# GridEye_STM32.net
KiCad netlist of a schematic drawn in Altium Designer
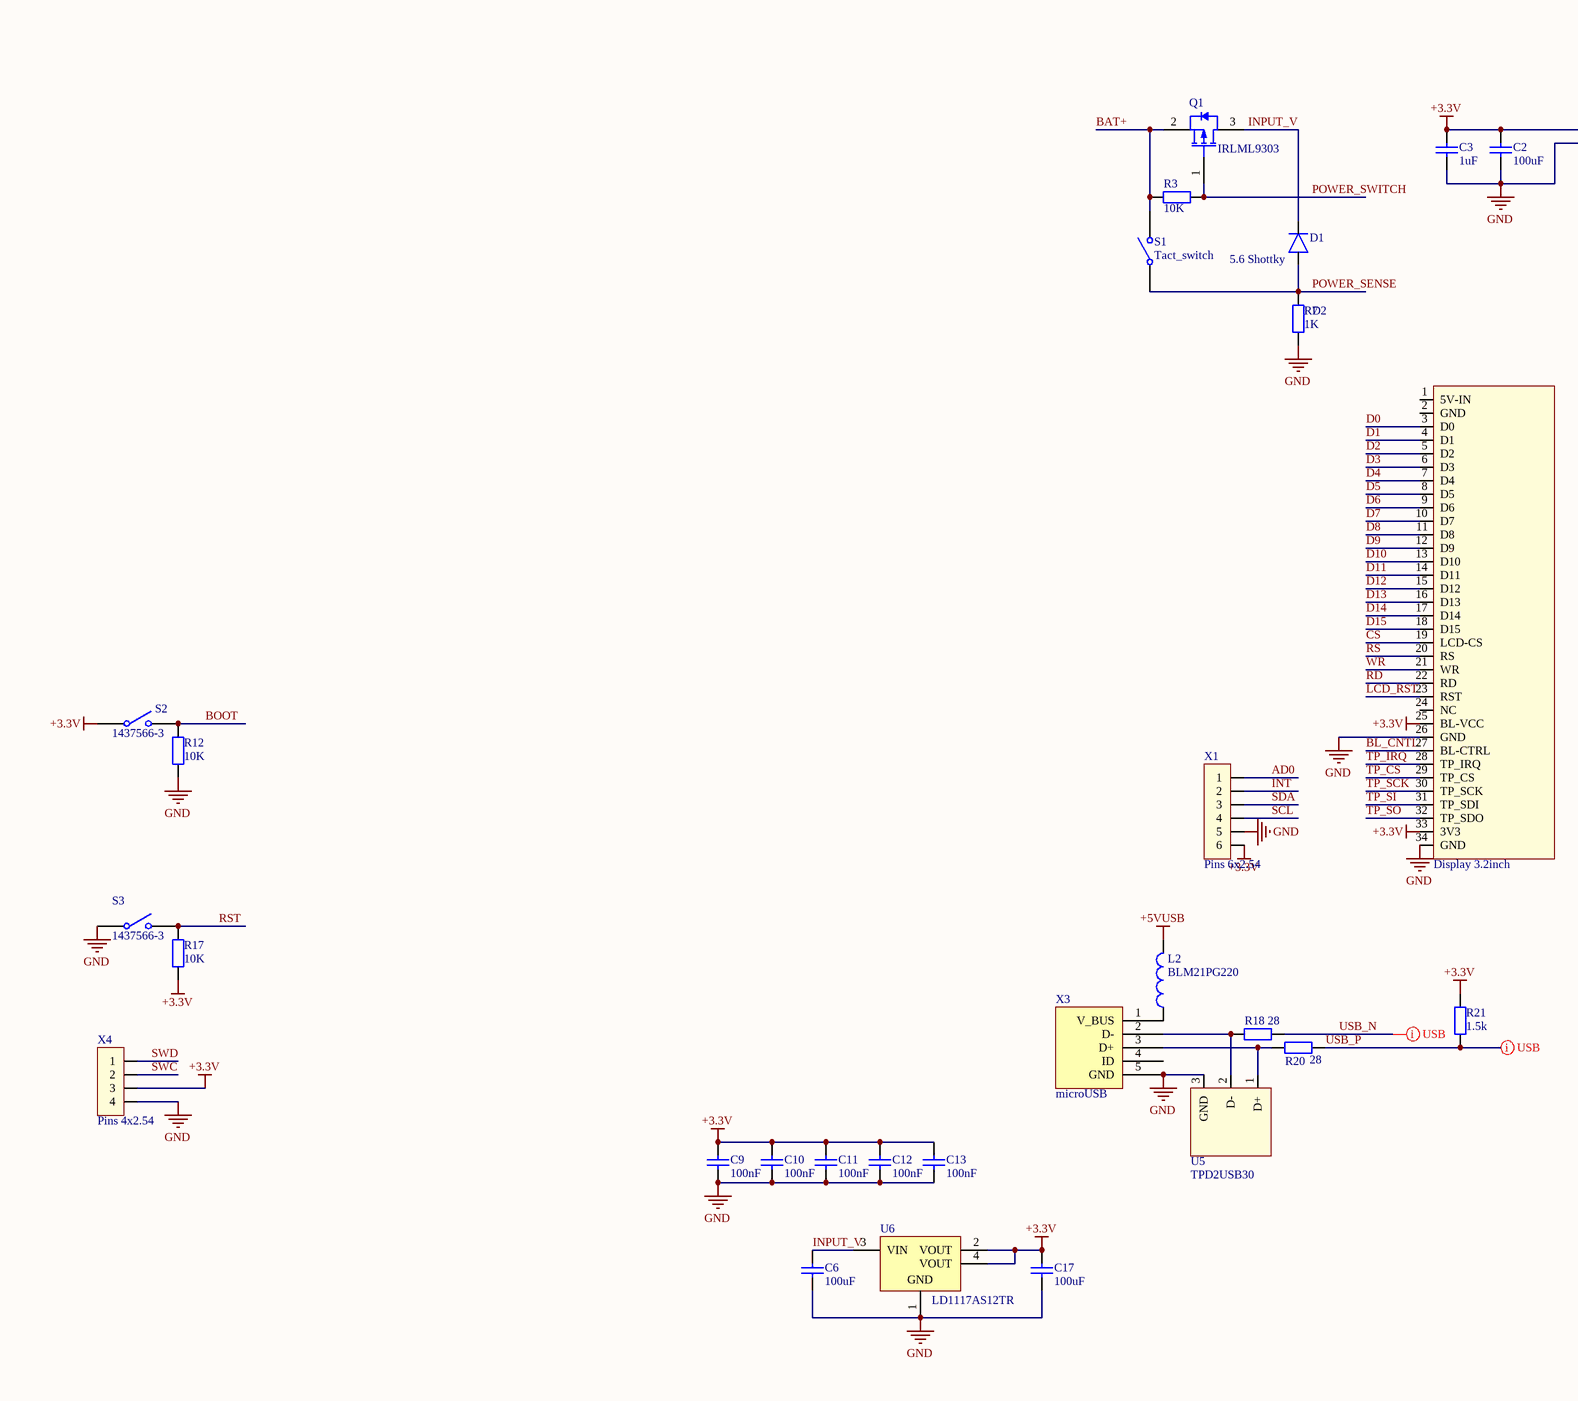
[diagram p0: GridEye_STM32.SchDoc, left]
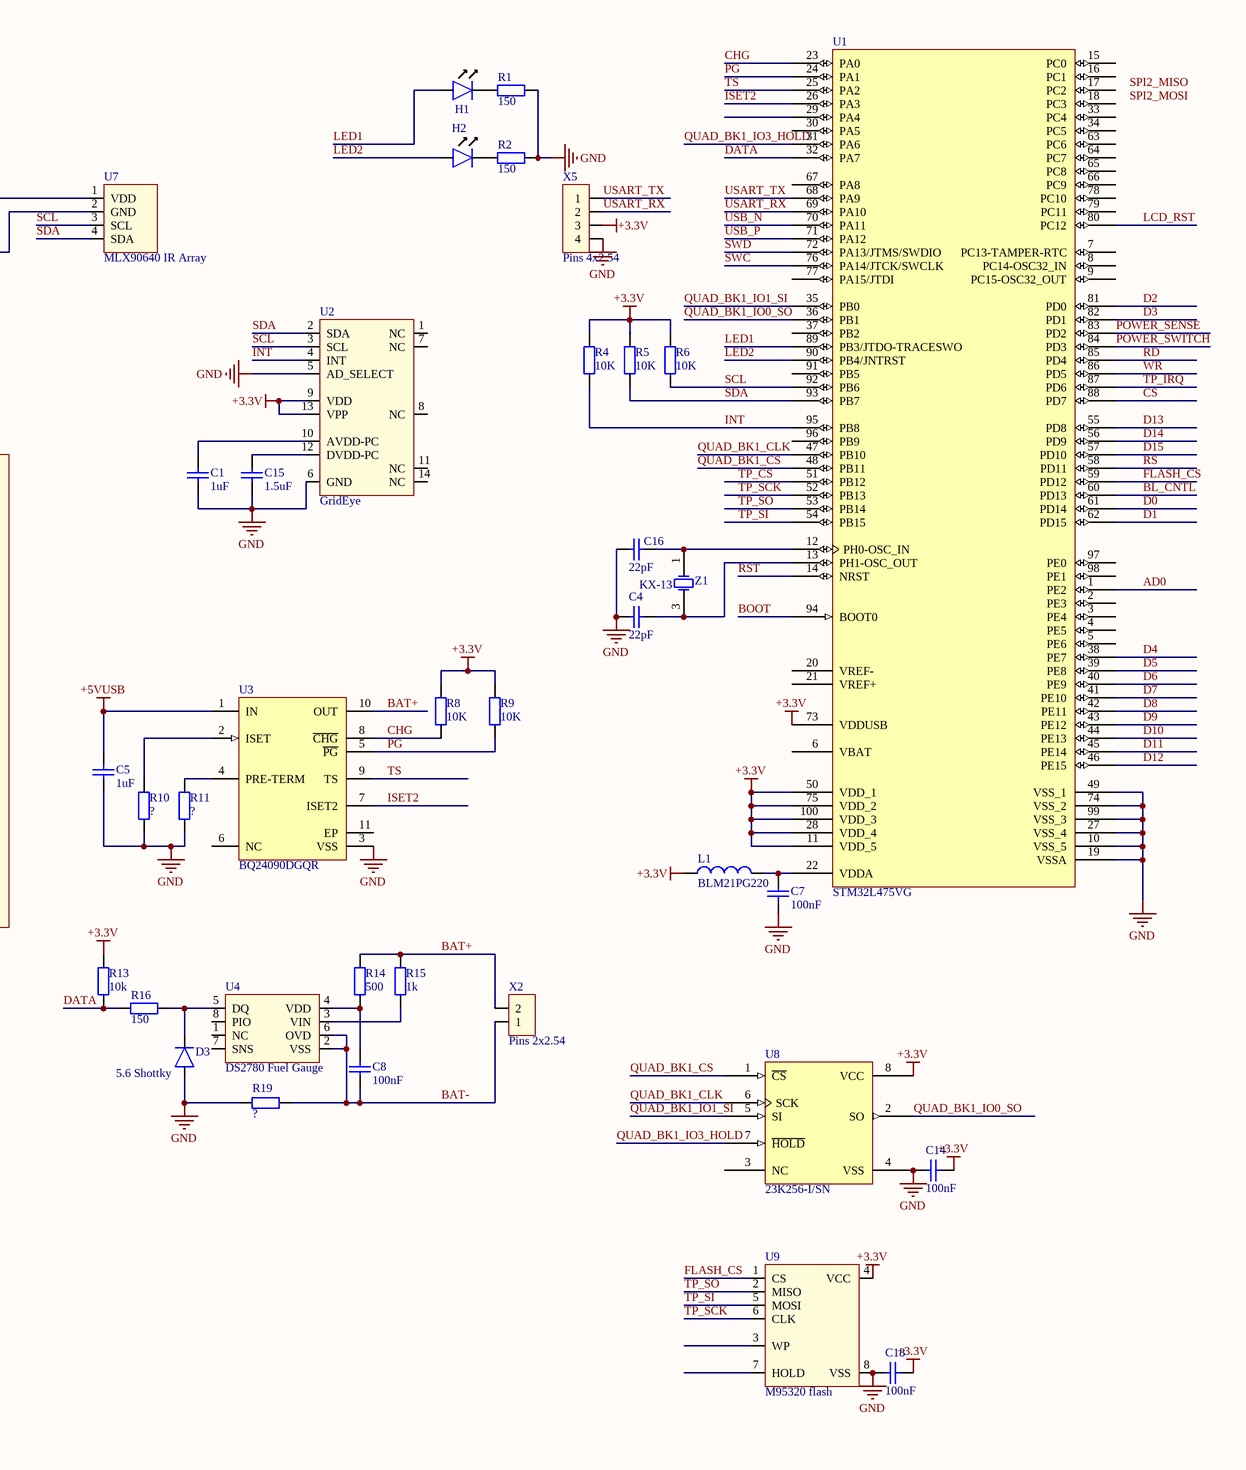
[diagram p1: GridEye_STM32.SchDoc, right]

(export (version "E")
  (design (tool "Eeschema 10.0.6"))
  (components
    (comp (ref "C1") (value "1uF") (footprint "C0603") (libsource (lib "A_H_sch_lib") (part "Condensator")))
    (comp (ref "C2") (value "100uF") (footprint "C0603") (libsource (lib "A_H_sch_lib") (part "Condensator")))
    (comp (ref "C3") (value "1uF") (footprint "C0603") (libsource (lib "A_H_sch_lib") (part "Condensator")))
    (comp (ref "C4") (value "22pF") (footprint "C0603") (libsource (lib "A_H_sch_lib") (part "Condensator")))
    (comp (ref "C5") (value "1uF") (footprint "C0603") (libsource (lib "A_H_sch_lib") (part "Condensator")))
    (comp (ref "C6") (value "100uF") (footprint "C0603") (libsource (lib "A_H_sch_lib") (part "Condensator")))
    (comp (ref "C7") (value "100nF") (footprint "C0603") (libsource (lib "A_H_sch_lib") (part "Condensator")))
    (comp (ref "C8") (value "100nF") (footprint "C0603") (libsource (lib "A_H_sch_lib") (part "Condensator")))
    (comp (ref "C9") (value "100nF") (footprint "C0603") (libsource (lib "A_H_sch_lib") (part "Condensator")))
    (comp (ref "C10")
      (value "100nF")
      (footprint "C0603")
      (libsource (lib "A_H_sch_lib") (part "Condensator"))
    )
    (comp (ref "C11")
      (value "100nF")
      (footprint "C0603")
      (libsource (lib "A_H_sch_lib") (part "Condensator"))
    )
    (comp (ref "C12")
      (value "100nF")
      (footprint "C0603")
      (libsource (lib "A_H_sch_lib") (part "Condensator"))
    )
    (comp (ref "C13")
      (value "100nF")
      (footprint "C0603")
      (libsource (lib "A_H_sch_lib") (part "Condensator"))
    )
    (comp (ref "C14")
      (value "100nF")
      (footprint "C0603")
      (libsource (lib "A_H_sch_lib") (part "Condensator"))
    )
    (comp (ref "C15")
      (value "1.5uF")
      (footprint "C0603")
      (libsource (lib "A_H_sch_lib") (part "Condensator"))
    )
    (comp (ref "C16") (value "22pF") (footprint "C0603") (libsource (lib "A_H_sch_lib") (part "Condensator")))
    (comp (ref "C17")
      (value "100uF")
      (footprint "C0603")
      (libsource (lib "A_H_sch_lib") (part "Condensator"))
    )
    (comp (ref "C18")
      (value "100nF")
      (footprint "C0603")
      (libsource (lib "A_H_sch_lib") (part "Condensator"))
    )
    (comp (ref "D1")
      (value "5.6 Shottky")
      (footprint "SMA_Diode")
      (libsource (lib "A_H_sch_lib") (part "Diod"))
    )
    (comp (ref "D2")
      (value "Display 3.2inch")
      (footprint "A_H_pcb_lib:Display_3.2inch")
      (libsource (lib "A_H_sch_lib") (part "Display_3.2inch"))
    )
    (comp (ref "D3")
      (value "5.6 Shottky")
      (footprint "SMA_Diode")
      (libsource (lib "A_H_sch_lib") (part "Diod"))
    )
    (comp (ref "H1") (value "LED_SMD") (footprint "C0603") (libsource (lib "A_H_sch_lib") (part "LED_SMD")))
    (comp (ref "H2") (value "LED_SMD") (footprint "C0603") (libsource (lib "A_H_sch_lib") (part "LED_SMD")))
    (comp (ref "L1")
      (value "BLM21PG220")
      (footprint "A_H_pcb_lib:L0603")
      (libsource (lib "A_H_sch_lib") (part "Inductance"))
    )
    (comp (ref "L2")
      (value "BLM21PG220")
      (footprint "A_H_pcb_lib:L0603")
      (libsource (lib "A_H_sch_lib") (part "Inductance"))
    )
    (comp (ref "Q1")
      (value "IRLML9303")
      (footprint "INF-PG-SOT23_N")
      (fields (field (name "MANUFACTURER") "Infineon") (field (name "PARTNUMBER") "BSS215P H6327"))
      (libsource (lib "Infineon_Power_MOSFET") (part "BSS215P H6327"))
    )
    (comp (ref "R1")
      (value "150")
      (footprint "A_H_pcb_lib:R0603")
      (libsource (lib "A_H_sch_lib") (part "Resistor"))
    )
    (comp (ref "R2")
      (value "150")
      (footprint "A_H_pcb_lib:R0603")
      (libsource (lib "A_H_sch_lib") (part "Resistor"))
    )
    (comp (ref "R3") (value "10K") (footprint "A_H_pcb_lib:R0603") (libsource (lib "") (part "Resistor_2")))
    (comp (ref "R4") (value "10K") (footprint "A_H_pcb_lib:R0603") (libsource (lib "") (part "Resistor_3")))
    (comp (ref "R5") (value "10K") (footprint "A_H_pcb_lib:R0603") (libsource (lib "") (part "Resistor_3")))
    (comp (ref "R6") (value "10K") (footprint "A_H_pcb_lib:R0603") (libsource (lib "") (part "Resistor_3")))
    (comp (ref "R7") (value "1K") (footprint "A_H_pcb_lib:R0603") (libsource (lib "") (part "Resistor_1")))
    (comp (ref "R8") (value "10K") (footprint "A_H_pcb_lib:R0603") (libsource (lib "") (part "Resistor_1")))
    (comp (ref "R9") (value "10K") (footprint "A_H_pcb_lib:R0603") (libsource (lib "") (part "Resistor_1")))
    (comp (ref "R10") (value "?") (footprint "A_H_pcb_lib:R0603") (libsource (lib "") (part "Resistor_1")))
    (comp (ref "R11") (value "?") (footprint "A_H_pcb_lib:R0603") (libsource (lib "") (part "Resistor_1")))
    (comp (ref "R12") (value "10K") (footprint "A_H_pcb_lib:R0603") (libsource (lib "") (part "Resistor_3")))
    (comp (ref "R13") (value "10k") (footprint "A_H_pcb_lib:R0603") (libsource (lib "") (part "Resistor_1")))
    (comp (ref "R14") (value "500") (footprint "A_H_pcb_lib:R0603") (libsource (lib "") (part "Resistor_1")))
    (comp (ref "R15") (value "1k") (footprint "A_H_pcb_lib:R0603") (libsource (lib "") (part "Resistor_1")))
    (comp (ref "R16")
      (value "150")
      (footprint "A_H_pcb_lib:R0603")
      (libsource (lib "A_H_sch_lib") (part "Resistor"))
    )
    (comp (ref "R17") (value "10K") (footprint "A_H_pcb_lib:R0603") (libsource (lib "") (part "Resistor_3")))
    (comp (ref "R18") (value "28") (footprint "A_H_pcb_lib:R0603") (libsource (lib "") (part "Resistor_2")))
    (comp (ref "R19") (value "?") (footprint "A_H_pcb_lib:R0603") (libsource (lib "") (part "Resistor_2")))
    (comp (ref "R20") (value "28") (footprint "A_H_pcb_lib:R0603") (libsource (lib "") (part "Resistor_2")))
    (comp (ref "R21") (value "1.5k") (footprint "A_H_pcb_lib:R0603") (libsource (lib "") (part "Resistor_3")))
    (comp (ref "S1")
      (value "Tact_switch")
      (footprint "A_H_pcb_lib:Tact_switch_DIP_angle_")
      (libsource (lib "A_H_sch_lib") (part "Tact_switch"))
    )
    (comp (ref "S2")
      (value "1437566-3")
      (footprint "Tact_switch_smd")
      (libsource (lib "A_H_sch_lib") (part "Tact_switch"))
    )
    (comp (ref "S3")
      (value "1437566-3")
      (footprint "Tact_switch_smd")
      (libsource (lib "A_H_sch_lib") (part "Tact_switch"))
    )
    (comp (ref "U1")
      (value "STM32L475VG")
      (footprint "LQFP100_N")
      (description "STM32 ARM-based 32-bit MCU with 1 Mbyte Flash, 100-pin LQFP")
      (fields (field (name "PUBLISHER") "Altium Limited"))
      (libsource (lib "Open_Parts_Library_Altium") (part "STM32L475VG"))
    )
    (comp (ref "U2")
      (value "GridEye")
      (footprint "A_H_pcb_lib:Panasonic GridEye")
      (libsource (lib "A_H_sch_lib") (part "Panasonic GridEye"))
    )
    (comp (ref "U3")
      (value "BQ24090DGQR")
      (footprint "DGQ10-1675X1445TP_N")
      (fields (field (name "MANUFACTURER") "Texas Instruments"))
      (libsource (lib "TI Power Management Battery Management") (part "BQ24090DGQR"))
    )
    (comp (ref "U4")
      (value "DS2780 Fuel Gauge")
      (footprint "A_H_pcb_lib:TSSOP-8")
      (libsource (lib "A_H_sch_lib") (part "DS2780+"))
    )
    (comp (ref "U5")
      (value "TPD2USB30")
      (footprint "A_H_pcb_lib:SOT_TPD2USB30")
      (description "Usb protector")
      (libsource (lib "A_H_sch_lib") (part "TPD2USB30"))
    )
    (comp (ref "U6")
      (value "LD1117AS12TR")
      (footprint "SOT-223_N")
      (description "1A, Low Drop Positive Voltage Regulator, 1.2V, 4-Pin SOT-223, Tape and Reel")
      (libsource (lib "STMicroelectronics Power Management Linear Regulator") (part "LD1117AS12TR"))
    )
    (comp (ref "U7")
      (value "MLX90640 IR Array")
      (footprint "A_H_pcb_lib:MLX90640")
      (libsource (lib "A_H_sch_lib") (part "MLX90640"))
    )
    (comp (ref "U8")
      (value "23K256-I/SN")
      (footprint "SOIC-SN8_N")
      (description "256K, 32768x8-bit, 3.6V SPI Serial SRAM, 8-Pin SOIC 3.9mm, Industrial Temperature")
      (fields (field (name "PUBLISHER") "Altium Limited"))
      (libsource (lib "Microchip Memory Serial SRAM") (part "23K256-I/SN"))
    )
    (comp (ref "U9")
      (value "M95320 flash")
      (footprint "A_H_pcb_lib:TSSOP-8")
      (libsource (lib "A_H_sch_lib") (part "M95320"))
    )
    (comp (ref "X1")
      (value "Pins 6x2.54")
      (footprint "Pins 6x2.54")
      (libsource (lib "A_H_sch_lib") (part "Pins 6x2.54"))
    )
    (comp (ref "X2")
      (value "Pins 2x2.54")
      (footprint "Pins 2x2.54")
      (libsource (lib "A_H_sch_lib") (part "Pins 2x2.54"))
    )
    (comp (ref "X3")
      (value "microUSB")
      (footprint "A_H_pcb_lib:microUSB")
      (libsource (lib "A_H_sch_lib") (part "microUSB"))
    )
    (comp (ref "X4")
      (value "Pins 4x2.54")
      (footprint "Pins 4x2.54")
      (libsource (lib "A_H_sch_lib") (part "Pins 4x2.54"))
    )
    (comp (ref "X5")
      (value "Pins 4x2.54")
      (footprint "Pins 4x2.54")
      (libsource (lib "A_H_sch_lib") (part "Pins 4x2.54"))
    )
    (comp (ref "Z1")
      (value "KX-13")
      (footprint "kx 13 12MHz")
      (libsource (lib "A_H_sch_lib") (part "KX 13 Geyer"))
    )
  )
  (nets
    (net (code "1") (name "+3.3V") (class "Default")
      (node (ref "C10") (pin "2") (pinfunction "2_2") (pintype "passive"))
      (node (ref "C11") (pin "2") (pinfunction "2_2") (pintype "passive"))
      (node (ref "C12") (pin "2") (pinfunction "2_2") (pintype "passive"))
      (node (ref "C13") (pin "2") (pinfunction "2_2") (pintype "passive"))
      (node (ref "C14") (pin "1") (pinfunction "1_1") (pintype "passive"))
      (node (ref "C17") (pin "2") (pinfunction "2_2") (pintype "passive"))
      (node (ref "C18") (pin "1") (pinfunction "1_1") (pintype "passive"))
      (node (ref "C2") (pin "1") (pinfunction "1_1") (pintype "passive"))
      (node (ref "C3") (pin "1") (pinfunction "1_1") (pintype "passive"))
      (node (ref "C9") (pin "2") (pinfunction "2_2") (pintype "passive"))
      (node (ref "D2") (pin "25") (pinfunction "BL-VCC_25") (pintype "passive"))
      (node (ref "D2") (pin "33") (pinfunction "3V3_33") (pintype "passive"))
      (node (ref "L1") (pin "1") (pinfunction "1_1") (pintype "passive"))
      (node (ref "R13") (pin "1") (pinfunction "1_1") (pintype "passive"))
      (node (ref "R17") (pin "1") (pinfunction "1_1") (pintype "passive"))
      (node (ref "R21") (pin "2") (pinfunction "2_2") (pintype "passive"))
      (node (ref "R4") (pin "2") (pinfunction "2_2") (pintype "passive"))
      (node (ref "R5") (pin "2") (pinfunction "2_2") (pintype "passive"))
      (node (ref "R6") (pin "2") (pinfunction "2_2") (pintype "passive"))
      (node (ref "R8") (pin "1") (pinfunction "1_1") (pintype "passive"))
      (node (ref "R9") (pin "1") (pinfunction "1_1") (pintype "passive"))
      (node (ref "S2") (pin "1") (pinfunction "COMMON_1") (pintype "passive"))
      (node (ref "U1") (pin "100") (pinfunction "VDD_3_100") (pintype "power_in"))
      (node (ref "U1") (pin "11") (pinfunction "VDD_5_11") (pintype "power_in"))
      (node (ref "U1") (pin "28") (pinfunction "VDD_4_28") (pintype "power_in"))
      (node (ref "U1") (pin "50") (pinfunction "VDD_1_50") (pintype "power_in"))
      (node (ref "U1") (pin "73") (pinfunction "VDDUSB_73") (pintype "passive"))
      (node (ref "U1") (pin "75") (pinfunction "VDD_2_75") (pintype "power_in"))
      (node (ref "U2") (pin "13") (pinfunction "VPP_13") (pintype "passive"))
      (node (ref "U2") (pin "9") (pinfunction "VDD_9") (pintype "passive"))
      (node (ref "U6") (pin "2") (pinfunction "VOUT_2") (pintype "power_in"))
      (node (ref "U6") (pin "4") (pinfunction "VOUT_4") (pintype "power_in"))
      (node (ref "U7") (pin "1") (pinfunction "VDD_1") (pintype "passive"))
      (node (ref "U8") (pin "8") (pinfunction "VCC_8") (pintype "power_in"))
      (node (ref "U9") (pin "4") (pinfunction "VCC_4") (pintype "passive"))
      (node (ref "X1") (pin "6") (pinfunction "6_6") (pintype "passive"))
      (node (ref "X4") (pin "3") (pinfunction "3_3") (pintype "passive"))
      (node (ref "X5") (pin "3") (pinfunction "3_3") (pintype "passive"))
    )
    (net (code "2") (name "+5VUSB") (class "Default")
      (node (ref "C5") (pin "2") (pinfunction "2_2") (pintype "passive"))
      (node (ref "L2") (pin "2") (pinfunction "2_2") (pintype "passive"))
      (node (ref "U3") (pin "1") (pinfunction "IN_1") (pintype "power_in"))
    )
    (net (code "3") (name "/AD0") (class "Default")
      (node (ref "U1") (pin "1") (pinfunction "PE2_1") (pintype "bidirectional"))
      (node (ref "X1") (pin "1") (pinfunction "1_1") (pintype "passive"))
    )
    (net (code "4") (name "/BAT+") (class "Default")
      (node (ref "Q1") (pin "2") (pinfunction "SOURCE_2") (pintype "passive"))
      (node (ref "R14") (pin "1") (pinfunction "1_1") (pintype "passive"))
      (node (ref "R15") (pin "1") (pinfunction "1_1") (pintype "passive"))
      (node (ref "R3") (pin "1") (pinfunction "1_1") (pintype "passive"))
      (node (ref "S1") (pin "2") (pinfunction "NO_2") (pintype "passive"))
      (node (ref "U3") (pin "10") (pinfunction "OUT_10") (pintype "power_in"))
      (node (ref "X2") (pin "2") (pinfunction "2_2") (pintype "passive"))
    )
    (net (code "5") (name "/BAT-") (class "Default")
      (node (ref "C8") (pin "1") (pinfunction "1_1") (pintype "passive"))
      (node (ref "R19") (pin "2") (pinfunction "2_2") (pintype "passive"))
      (node (ref "U4") (pin "2") (pinfunction "VSS_2") (pintype "passive"))
      (node (ref "U4") (pin "6") (pinfunction "OVD_6") (pintype "passive"))
      (node (ref "X2") (pin "1") (pinfunction "1_1") (pintype "passive"))
    )
    (net (code "6") (name "/BL_CNTL") (class "Default")
      (node (ref "D2") (pin "27") (pinfunction "BL-CTRL_27") (pintype "passive"))
      (node (ref "U1") (pin "60") (pinfunction "PD13_60") (pintype "bidirectional"))
    )
    (net (code "7") (name "/BOOT") (class "Default")
      (node (ref "R12") (pin "2") (pinfunction "2_2") (pintype "passive"))
      (node (ref "S2") (pin "2") (pinfunction "NO_2") (pintype "passive"))
      (node (ref "U1") (pin "94") (pinfunction "BOOT0_94") (pintype "input"))
    )
    (net (code "8") (name "/CHG") (class "Default")
      (node (ref "R8") (pin "2") (pinfunction "2_2") (pintype "passive"))
      (node (ref "U1") (pin "23") (pinfunction "PA0_23") (pintype "bidirectional"))
      (node (ref "U3") (pin "8") (pinfunction "~{CHG}_8") (pintype "tri_state"))
    )
    (net (code "9") (name "/CS") (class "Default")
      (node (ref "D2") (pin "19") (pinfunction "LCD-CS_19") (pintype "passive"))
      (node (ref "U1") (pin "88") (pinfunction "PD7_88") (pintype "bidirectional"))
    )
    (net (code "10") (name "/D0") (class "Default")
      (node (ref "D2") (pin "3") (pinfunction "D0_3") (pintype "passive"))
      (node (ref "U1") (pin "61") (pinfunction "PD14_61") (pintype "bidirectional"))
    )
    (net (code "11") (name "/D1") (class "Default")
      (node (ref "D2") (pin "4") (pinfunction "D1_4") (pintype "passive"))
      (node (ref "U1") (pin "62") (pinfunction "PD15_62") (pintype "bidirectional"))
    )
    (net (code "12") (name "/D2") (class "Default")
      (node (ref "D2") (pin "5") (pinfunction "D2_5") (pintype "passive"))
      (node (ref "U1") (pin "81") (pinfunction "PD0_81") (pintype "bidirectional"))
    )
    (net (code "13") (name "/D3") (class "Default")
      (node (ref "D2") (pin "6") (pinfunction "D3_6") (pintype "passive"))
      (node (ref "U1") (pin "82") (pinfunction "PD1_82") (pintype "bidirectional"))
    )
    (net (code "14") (name "/D4") (class "Default")
      (node (ref "D2") (pin "7") (pinfunction "D4_7") (pintype "passive"))
      (node (ref "U1") (pin "38") (pinfunction "PE7_38") (pintype "bidirectional"))
    )
    (net (code "15") (name "/D5") (class "Default")
      (node (ref "D2") (pin "8") (pinfunction "D5_8") (pintype "passive"))
      (node (ref "U1") (pin "39") (pinfunction "PE8_39") (pintype "bidirectional"))
    )
    (net (code "16") (name "/D6") (class "Default")
      (node (ref "D2") (pin "9") (pinfunction "D6_9") (pintype "passive"))
      (node (ref "U1") (pin "40") (pinfunction "PE9_40") (pintype "bidirectional"))
    )
    (net (code "17") (name "/D7") (class "Default")
      (node (ref "D2") (pin "10") (pinfunction "D7_10") (pintype "passive"))
      (node (ref "U1") (pin "41") (pinfunction "PE10_41") (pintype "bidirectional"))
    )
    (net (code "18") (name "/D8") (class "Default")
      (node (ref "D2") (pin "11") (pinfunction "D8_11") (pintype "passive"))
      (node (ref "U1") (pin "42") (pinfunction "PE11_42") (pintype "bidirectional"))
    )
    (net (code "19") (name "/D9") (class "Default")
      (node (ref "D2") (pin "12") (pinfunction "D9_12") (pintype "passive"))
      (node (ref "U1") (pin "43") (pinfunction "PE12_43") (pintype "bidirectional"))
    )
    (net (code "20") (name "/D10") (class "Default")
      (node (ref "D2") (pin "13") (pinfunction "D10_13") (pintype "passive"))
      (node (ref "U1") (pin "44") (pinfunction "PE13_44") (pintype "bidirectional"))
    )
    (net (code "21") (name "/D11") (class "Default")
      (node (ref "D2") (pin "14") (pinfunction "D11_14") (pintype "passive"))
      (node (ref "U1") (pin "45") (pinfunction "PE14_45") (pintype "bidirectional"))
    )
    (net (code "22") (name "/D12") (class "Default")
      (node (ref "D2") (pin "15") (pinfunction "D12_15") (pintype "passive"))
      (node (ref "U1") (pin "46") (pinfunction "PE15_46") (pintype "bidirectional"))
    )
    (net (code "23") (name "/D13") (class "Default")
      (node (ref "D2") (pin "16") (pinfunction "D13_16") (pintype "passive"))
      (node (ref "U1") (pin "55") (pinfunction "PD8_55") (pintype "bidirectional"))
    )
    (net (code "24") (name "/D14") (class "Default")
      (node (ref "D2") (pin "17") (pinfunction "D14_17") (pintype "passive"))
      (node (ref "U1") (pin "56") (pinfunction "PD9_56") (pintype "bidirectional"))
    )
    (net (code "25") (name "/D15") (class "Default")
      (node (ref "D2") (pin "18") (pinfunction "D15_18") (pintype "passive"))
      (node (ref "U1") (pin "57") (pinfunction "PD10_57") (pintype "bidirectional"))
    )
    (net (code "26") (name "/DATA") (class "Default")
      (node (ref "R13") (pin "2") (pinfunction "2_2") (pintype "passive"))
      (node (ref "R16") (pin "2") (pinfunction "2_2") (pintype "passive"))
      (node (ref "U1") (pin "32") (pinfunction "PA7_32") (pintype "bidirectional"))
    )
    (net (code "27") (name "/FLASH_CS") (class "Default")
      (node (ref "U1") (pin "59") (pinfunction "PD12_59") (pintype "bidirectional"))
      (node (ref "U9") (pin "1") (pinfunction "CS_1") (pintype "passive"))
    )
    (net (code "28") (name "/INPUT_V") (class "Default")
      (node (ref "C6") (pin "2") (pinfunction "2_2") (pintype "passive"))
      (node (ref "D1") (pin "2") (pinfunction "2_2") (pintype "passive"))
      (node (ref "Q1") (pin "3") (pinfunction "DRAIN_3") (pintype "passive"))
      (node (ref "U6") (pin "3") (pinfunction "VIN_3") (pintype "power_in"))
    )
    (net (code "29") (name "/INT") (class "Default")
      (node (ref "R4") (pin "1") (pinfunction "1_1") (pintype "passive"))
      (node (ref "U1") (pin "95") (pinfunction "PB8_95") (pintype "bidirectional"))
      (node (ref "U2") (pin "4") (pinfunction "INT_4") (pintype "passive"))
      (node (ref "X1") (pin "2") (pinfunction "2_2") (pintype "passive"))
    )
    (net (code "30") (name "/ISET2") (class "Default")
      (node (ref "U1") (pin "26") (pinfunction "PA3_26") (pintype "bidirectional"))
      (node (ref "U3") (pin "7") (pinfunction "ISET2_7") (pintype "passive"))
    )
    (net (code "31") (name "/LCD_RST") (class "Default")
      (node (ref "D2") (pin "23") (pinfunction "RST_23") (pintype "passive"))
      (node (ref "U1") (pin "80") (pinfunction "PC12_80") (pintype "bidirectional"))
    )
    (net (code "32") (name "/LED1") (class "Default")
      (node (ref "H1") (pin "1") (pinfunction "1_1") (pintype "passive"))
      (node (ref "U1") (pin "89") (pinfunction "PB3/JTDO-TRACESWO_89") (pintype "bidirectional"))
    )
    (net (code "33") (name "/LED2") (class "Default")
      (node (ref "H2") (pin "1") (pinfunction "1_1") (pintype "passive"))
      (node (ref "U1") (pin "90") (pinfunction "PB4/JNTRST_90") (pintype "bidirectional"))
    )
    (net (code "34") (name "/PG") (class "Default")
      (node (ref "R9") (pin "2") (pinfunction "2_2") (pintype "passive"))
      (node (ref "U1") (pin "24") (pinfunction "PA1_24") (pintype "bidirectional"))
      (node (ref "U3") (pin "5") (pinfunction "~{PG}_5") (pintype "tri_state"))
    )
    (net (code "35") (name "/POWER_SENSE") (class "Default")
      (node (ref "D1") (pin "1") (pinfunction "1_1") (pintype "passive"))
      (node (ref "R7") (pin "1") (pinfunction "1_1") (pintype "passive"))
      (node (ref "S1") (pin "1") (pinfunction "COMMON_1") (pintype "passive"))
      (node (ref "U1") (pin "83") (pinfunction "PD2_83") (pintype "bidirectional"))
    )
    (net (code "36") (name "/POWER_SWITCH") (class "Default")
      (node (ref "Q1") (pin "1") (pinfunction "GATE_1") (pintype "passive"))
      (node (ref "R3") (pin "2") (pinfunction "2_2") (pintype "passive"))
      (node (ref "U1") (pin "84") (pinfunction "PD3_84") (pintype "bidirectional"))
    )
    (net (code "37") (name "/QUAD_BK1_CLK") (class "Default")
      (node (ref "U1") (pin "47") (pinfunction "PB10_47") (pintype "bidirectional"))
      (node (ref "U8") (pin "6") (pinfunction "SCK_6") (pintype "input"))
    )
    (net (code "38") (name "/QUAD_BK1_CS") (class "Default")
      (node (ref "U1") (pin "48") (pinfunction "PB11_48") (pintype "bidirectional"))
      (node (ref "U8") (pin "1") (pinfunction "~{CS}_1") (pintype "input"))
    )
    (net (code "39") (name "/QUAD_BK1_IO0_SO") (class "Default")
      (node (ref "U1") (pin "36") (pinfunction "PB1_36") (pintype "bidirectional"))
      (node (ref "U8") (pin "2") (pinfunction "SO_2") (pintype "output"))
    )
    (net (code "40") (name "/QUAD_BK1_IO1_SI") (class "Default")
      (node (ref "U1") (pin "35") (pinfunction "PB0_35") (pintype "bidirectional"))
      (node (ref "U8") (pin "5") (pinfunction "SI_5") (pintype "input"))
    )
    (net (code "41") (name "/QUAD_BK1_IO3_HOLD") (class "Default")
      (node (ref "U1") (pin "31") (pinfunction "PA6_31") (pintype "bidirectional"))
      (node (ref "U8") (pin "7") (pinfunction "~{HOLD}_7") (pintype "input"))
    )
    (net (code "42") (name "/RD") (class "Default")
      (node (ref "D2") (pin "22") (pinfunction "RD_22") (pintype "passive"))
      (node (ref "U1") (pin "85") (pinfunction "PD4_85") (pintype "bidirectional"))
    )
    (net (code "43") (name "/RS") (class "Default")
      (node (ref "D2") (pin "20") (pinfunction "RS_20") (pintype "passive"))
      (node (ref "U1") (pin "58") (pinfunction "PD11_58") (pintype "bidirectional"))
    )
    (net (code "44") (name "/RST") (class "Default")
      (node (ref "R17") (pin "2") (pinfunction "2_2") (pintype "passive"))
      (node (ref "S3") (pin "2") (pinfunction "NO_2") (pintype "passive"))
      (node (ref "U1") (pin "14") (pinfunction "NRST_14") (pintype "bidirectional"))
    )
    (net (code "45") (name "/SCL") (class "Default")
      (node (ref "R6") (pin "1") (pinfunction "1_1") (pintype "passive"))
      (node (ref "U1") (pin "92") (pinfunction "PB6_92") (pintype "bidirectional"))
      (node (ref "U2") (pin "3") (pinfunction "SCL_3") (pintype "passive"))
      (node (ref "U7") (pin "3") (pinfunction "SCL_3") (pintype "passive"))
      (node (ref "X1") (pin "4") (pinfunction "4_4") (pintype "passive"))
    )
    (net (code "46") (name "/SDA") (class "Default")
      (node (ref "R5") (pin "1") (pinfunction "1_1") (pintype "passive"))
      (node (ref "U1") (pin "93") (pinfunction "PB7_93") (pintype "bidirectional"))
      (node (ref "U2") (pin "2") (pinfunction "SDA_2") (pintype "passive"))
      (node (ref "U7") (pin "4") (pinfunction "SDA_4") (pintype "passive"))
      (node (ref "X1") (pin "3") (pinfunction "3_3") (pintype "passive"))
    )
    (net (code "49") (name "/SWC") (class "Default")
      (node (ref "U1") (pin "76") (pinfunction "PA14/JTCK/SWCLK_76") (pintype "bidirectional"))
      (node (ref "X4") (pin "2") (pinfunction "2_2") (pintype "passive"))
    )
    (net (code "50") (name "/SWD") (class "Default")
      (node (ref "U1") (pin "72") (pinfunction "PA13/JTMS/SWDIO_72") (pintype "bidirectional"))
      (node (ref "X4") (pin "1") (pinfunction "1_1") (pintype "passive"))
    )
    (net (code "51") (name "/TP_CS") (class "Default")
      (node (ref "D2") (pin "29") (pinfunction "TP_CS_29") (pintype "passive"))
      (node (ref "U1") (pin "51") (pinfunction "PB12_51") (pintype "bidirectional"))
    )
    (net (code "52") (name "/TP_IRQ") (class "Default")
      (node (ref "D2") (pin "28") (pinfunction "TP_IRQ_28") (pintype "passive"))
      (node (ref "U1") (pin "87") (pinfunction "PD6_87") (pintype "bidirectional"))
    )
    (net (code "53") (name "/TP_SCK") (class "Default")
      (node (ref "D2") (pin "30") (pinfunction "TP_SCK_30") (pintype "passive"))
      (node (ref "U1") (pin "52") (pinfunction "PB13_52") (pintype "bidirectional"))
      (node (ref "U9") (pin "6") (pinfunction "CLK_6") (pintype "passive"))
    )
    (net (code "54") (name "/TP_SI") (class "Default")
      (node (ref "D2") (pin "31") (pinfunction "TP_SDI_31") (pintype "passive"))
      (node (ref "U1") (pin "54") (pinfunction "PB15_54") (pintype "bidirectional"))
      (node (ref "U9") (pin "5") (pinfunction "MOSI_5") (pintype "passive"))
    )
    (net (code "55") (name "/TP_SO") (class "Default")
      (node (ref "D2") (pin "32") (pinfunction "TP_SDO_32") (pintype "passive"))
      (node (ref "U1") (pin "53") (pinfunction "PB14_53") (pintype "bidirectional"))
      (node (ref "U9") (pin "2") (pinfunction "MISO_2") (pintype "passive"))
    )
    (net (code "56") (name "/TS") (class "Default")
      (node (ref "U1") (pin "25") (pinfunction "PA2_25") (pintype "bidirectional"))
      (node (ref "U3") (pin "9") (pinfunction "TS_9") (pintype "passive"))
    )
    (net (code "57") (name "/USART_RX") (class "Default")
      (node (ref "U1") (pin "69") (pinfunction "PA10_69") (pintype "bidirectional"))
      (node (ref "X5") (pin "2") (pinfunction "2_2") (pintype "passive"))
    )
    (net (code "58") (name "/USART_TX") (class "Default")
      (node (ref "U1") (pin "68") (pinfunction "PA9_68") (pintype "bidirectional"))
      (node (ref "X5") (pin "1") (pinfunction "1_1") (pintype "passive"))
    )
    (net (code "59") (name "/USB_N") (class "Default")
      (node (ref "R18") (pin "2") (pinfunction "2_2") (pintype "passive"))
      (node (ref "U1") (pin "70") (pinfunction "PA11_70") (pintype "bidirectional"))
    )
    (net (code "60") (name "/USB_P") (class "Default")
      (node (ref "R20") (pin "2") (pinfunction "2_2") (pintype "passive"))
      (node (ref "R21") (pin "1") (pinfunction "1_1") (pintype "passive"))
      (node (ref "U1") (pin "71") (pinfunction "PA12_71") (pintype "bidirectional"))
    )
    (net (code "61") (name "/WR") (class "Default")
      (node (ref "D2") (pin "21") (pinfunction "WR_21") (pintype "passive"))
      (node (ref "U1") (pin "86") (pinfunction "PD5_86") (pintype "bidirectional"))
    )
    (net (code "62") (name "GND") (class "Default")
      (node (ref "C1") (pin "2") (pinfunction "2_2") (pintype "passive"))
      (node (ref "C10") (pin "1") (pinfunction "1_1") (pintype "passive"))
      (node (ref "C11") (pin "1") (pinfunction "1_1") (pintype "passive"))
      (node (ref "C12") (pin "1") (pinfunction "1_1") (pintype "passive"))
      (node (ref "C13") (pin "1") (pinfunction "1_1") (pintype "passive"))
      (node (ref "C14") (pin "2") (pinfunction "2_2") (pintype "passive"))
      (node (ref "C15") (pin "2") (pinfunction "2_2") (pintype "passive"))
      (node (ref "C16") (pin "2") (pinfunction "2_2") (pintype "passive"))
      (node (ref "C17") (pin "1") (pinfunction "1_1") (pintype "passive"))
      (node (ref "C18") (pin "2") (pinfunction "2_2") (pintype "passive"))
      (node (ref "C2") (pin "2") (pinfunction "2_2") (pintype "passive"))
      (node (ref "C3") (pin "2") (pinfunction "2_2") (pintype "passive"))
      (node (ref "C4") (pin "2") (pinfunction "2_2") (pintype "passive"))
      (node (ref "C5") (pin "1") (pinfunction "1_1") (pintype "passive"))
      (node (ref "C6") (pin "1") (pinfunction "1_1") (pintype "passive"))
      (node (ref "C7") (pin "1") (pinfunction "1_1") (pintype "passive"))
      (node (ref "C9") (pin "1") (pinfunction "1_1") (pintype "passive"))
      (node (ref "D2") (pin "26") (pinfunction "GND_26") (pintype "passive"))
      (node (ref "D2") (pin "34") (pinfunction "GND_34") (pintype "passive"))
      (node (ref "D3") (pin "1") (pinfunction "1_1") (pintype "passive"))
      (node (ref "R1") (pin "1") (pinfunction "1_1") (pintype "passive"))
      (node (ref "R10") (pin "2") (pinfunction "2_2") (pintype "passive"))
      (node (ref "R11") (pin "2") (pinfunction "2_2") (pintype "passive"))
      (node (ref "R12") (pin "1") (pinfunction "1_1") (pintype "passive"))
      (node (ref "R19") (pin "1") (pinfunction "1_1") (pintype "passive"))
      (node (ref "R2") (pin "1") (pinfunction "1_1") (pintype "passive"))
      (node (ref "R7") (pin "2") (pinfunction "2_2") (pintype "passive"))
      (node (ref "S3") (pin "1") (pinfunction "COMMON_1") (pintype "passive"))
      (node (ref "U1") (pin "10") (pinfunction "VSS_5_10") (pintype "power_in"))
      (node (ref "U1") (pin "19") (pinfunction "VSSA_19") (pintype "power_in"))
      (node (ref "U1") (pin "27") (pinfunction "VSS_4_27") (pintype "power_in"))
      (node (ref "U1") (pin "49") (pinfunction "VSS_1_49") (pintype "power_in"))
      (node (ref "U1") (pin "74") (pinfunction "VSS_2_74") (pintype "power_in"))
      (node (ref "U1") (pin "99") (pinfunction "VSS_3_99") (pintype "power_in"))
      (node (ref "U2") (pin "5") (pinfunction "AD_SELECT_5") (pintype "passive"))
      (node (ref "U2") (pin "6") (pinfunction "GND_6") (pintype "passive"))
      (node (ref "U3") (pin "3") (pinfunction "VSS_3") (pintype "power_in"))
      (node (ref "U5") (pin "3") (pinfunction "GND_3") (pintype "passive"))
      (node (ref "U6") (pin "1") (pinfunction "GND_1") (pintype "power_in"))
      (node (ref "U7") (pin "2") (pinfunction "GND_2") (pintype "passive"))
      (node (ref "U8") (pin "4") (pinfunction "VSS_4") (pintype "power_in"))
      (node (ref "U9") (pin "8") (pinfunction "VSS_8") (pintype "passive"))
      (node (ref "X1") (pin "5") (pinfunction "5_5") (pintype "passive"))
      (node (ref "X3") (pin "5") (pinfunction "GND_5") (pintype "passive"))
      (node (ref "X4") (pin "4") (pinfunction "4_4") (pintype "passive"))
      (node (ref "X5") (pin "4") (pinfunction "4_4") (pintype "passive"))
    )
    (net (code "63") (name "Net-(H1-Pad2)") (class "Default")
      (node (ref "H1") (pin "2") (pinfunction "2_2") (pintype "passive"))
      (node (ref "R1") (pin "2") (pinfunction "2_2") (pintype "passive"))
    )
    (net (code "64") (name "Net-(H2-Pad2)") (class "Default")
      (node (ref "H2") (pin "2") (pinfunction "2_2") (pintype "passive"))
      (node (ref "R2") (pin "2") (pinfunction "2_2") (pintype "passive"))
    )
    (net (code "65") (name "Net-(U1-PH0-OSC_IN)") (class "Default")
      (node (ref "C16") (pin "1") (pinfunction "1_1") (pintype "passive"))
      (node (ref "U1") (pin "12") (pinfunction "PH0-OSC_IN_12") (pintype "bidirectional"))
      (node (ref "Z1") (pin "1") (pinfunction "OSC1_1") (pintype "passive"))
    )
    (net (code "66") (name "Net-(U1-PH1-OSC_OUT)") (class "Default")
      (node (ref "C4") (pin "1") (pinfunction "1_1") (pintype "passive"))
      (node (ref "U1") (pin "13") (pinfunction "PH1-OSC_OUT_13") (pintype "bidirectional"))
      (node (ref "Z1") (pin "3") (pinfunction "OSC2_3") (pintype "passive"))
    )
    (net (code "67") (name "Net-(U1-VDDA)") (class "Default")
      (node (ref "C7") (pin "2") (pinfunction "2_2") (pintype "passive"))
      (node (ref "L1") (pin "2") (pinfunction "2_2") (pintype "passive"))
      (node (ref "U1") (pin "22") (pinfunction "VDDA_22") (pintype "power_in"))
    )
    (net (code "68") (name "Net-(U2-AVDD-PC)") (class "Default")
      (node (ref "C1") (pin "1") (pinfunction "1_1") (pintype "passive"))
      (node (ref "U2") (pin "10") (pinfunction "AVDD-PC_10") (pintype "passive"))
    )
    (net (code "69") (name "Net-(U2-DVDD-PC)") (class "Default")
      (node (ref "C15") (pin "1") (pinfunction "1_1") (pintype "passive"))
      (node (ref "U2") (pin "12") (pinfunction "DVDD-PC_12") (pintype "passive"))
    )
    (net (code "70") (name "Net-(U3-ISET)") (class "Default")
      (node (ref "R10") (pin "1") (pinfunction "1_1") (pintype "passive"))
      (node (ref "U3") (pin "2") (pinfunction "ISET_2") (pintype "input"))
    )
    (net (code "71") (name "Net-(U3-PRE-TERM)") (class "Default")
      (node (ref "R11") (pin "1") (pinfunction "1_1") (pintype "passive"))
      (node (ref "U3") (pin "4") (pinfunction "PRE-TERM_4") (pintype "passive"))
    )
    (net (code "72") (name "Net-(U4-DQ)") (class "Default")
      (node (ref "D3") (pin "2") (pinfunction "2_2") (pintype "passive"))
      (node (ref "R16") (pin "1") (pinfunction "1_1") (pintype "passive"))
      (node (ref "U4") (pin "5") (pinfunction "DQ_5") (pintype "passive"))
    )
    (net (code "73") (name "Net-(U4-VDD)") (class "Default")
      (node (ref "C8") (pin "2") (pinfunction "2_2") (pintype "passive"))
      (node (ref "R14") (pin "2") (pinfunction "2_2") (pintype "passive"))
      (node (ref "U4") (pin "4") (pinfunction "VDD_4") (pintype "passive"))
    )
    (net (code "74") (name "Net-(U4-VIN)") (class "Default")
      (node (ref "R15") (pin "2") (pinfunction "2_2") (pintype "passive"))
      (node (ref "U4") (pin "3") (pinfunction "VIN_3") (pintype "passive"))
    )
    (net (code "75") (name "Net-(U5-D+)") (class "Default")
      (node (ref "R20") (pin "1") (pinfunction "1_1") (pintype "passive"))
      (node (ref "U5") (pin "1") (pinfunction "D+_1") (pintype "passive"))
      (node (ref "X3") (pin "3") (pinfunction "D+_3") (pintype "passive"))
    )
    (net (code "76") (name "Net-(U5-D-)") (class "Default")
      (node (ref "R18") (pin "1") (pinfunction "1_1") (pintype "passive"))
      (node (ref "U5") (pin "2") (pinfunction "D-_2") (pintype "passive"))
      (node (ref "X3") (pin "2") (pinfunction "D-_2") (pintype "passive"))
    )
    (net (code "77") (name "Net-(X3-V_BUS)") (class "Default")
      (node (ref "L2") (pin "1") (pinfunction "1_1") (pintype "passive"))
      (node (ref "X3") (pin "1") (pinfunction "V_BUS_1") (pintype "passive"))
    )
    (net (code "78") (name "unconnected-(D2-5V-IN-Pad1)") (class "Default")
      (node (ref "D2") (pin "1") (pinfunction "5V-IN_1") (pintype "passive"))
    )
    (net (code "79") (name "unconnected-(D2-GND-Pad2)") (class "Default")
      (node (ref "D2") (pin "2") (pinfunction "GND_2") (pintype "passive"))
    )
    (net (code "80") (name "unconnected-(D2-NC-Pad24)") (class "Default")
      (node (ref "D2") (pin "24") (pinfunction "NC_24") (pintype "passive"))
    )
    (net (code "81") (name "unconnected-(U1-PA4-Pad29)") (class "Default")
      (node (ref "U1") (pin "29") (pinfunction "PA4_29") (pintype "bidirectional"))
    )
    (net (code "82") (name "unconnected-(U1-PA5-Pad30)") (class "Default")
      (node (ref "U1") (pin "30") (pinfunction "PA5_30") (pintype "bidirectional"))
    )
    (net (code "83") (name "unconnected-(U1-PA8-Pad67)") (class "Default")
      (node (ref "U1") (pin "67") (pinfunction "PA8_67") (pintype "bidirectional"))
    )
    (net (code "84") (name "unconnected-(U1-PA15{slash}JTDI-Pad77)") (class "Default")
      (node (ref "U1") (pin "77") (pinfunction "PA15/JTDI_77") (pintype "bidirectional"))
    )
    (net (code "85") (name "unconnected-(U1-PB2-Pad37)") (class "Default")
      (node (ref "U1") (pin "37") (pinfunction "PB2_37") (pintype "bidirectional"))
    )
    (net (code "86") (name "unconnected-(U1-PB5-Pad91)") (class "Default")
      (node (ref "U1") (pin "91") (pinfunction "PB5_91") (pintype "bidirectional"))
    )
    (net (code "87") (name "unconnected-(U1-PB9-Pad96)") (class "Default")
      (node (ref "U1") (pin "96") (pinfunction "PB9_96") (pintype "bidirectional"))
    )
    (net (code "88") (name "unconnected-(U1-PC0-Pad15)") (class "Default")
      (node (ref "U1") (pin "15") (pinfunction "PC0_15") (pintype "bidirectional"))
    )
    (net (code "89") (name "unconnected-(U1-PC1-Pad16)") (class "Default")
      (node (ref "U1") (pin "16") (pinfunction "PC1_16") (pintype "bidirectional"))
    )
    (net (code "90") (name "unconnected-(U1-PC2-Pad17)") (class "Default")
      (node (ref "U1") (pin "17") (pinfunction "PC2_17") (pintype "bidirectional"))
    )
    (net (code "91") (name "unconnected-(U1-PC3-Pad18)") (class "Default")
      (node (ref "U1") (pin "18") (pinfunction "PC3_18") (pintype "bidirectional"))
    )
    (net (code "92") (name "unconnected-(U1-PC4-Pad33)") (class "Default")
      (node (ref "U1") (pin "33") (pinfunction "PC4_33") (pintype "bidirectional"))
    )
    (net (code "93") (name "unconnected-(U1-PC5-Pad34)") (class "Default")
      (node (ref "U1") (pin "34") (pinfunction "PC5_34") (pintype "bidirectional"))
    )
    (net (code "94") (name "unconnected-(U1-PC6-Pad63)") (class "Default")
      (node (ref "U1") (pin "63") (pinfunction "PC6_63") (pintype "bidirectional"))
    )
    (net (code "95") (name "unconnected-(U1-PC7-Pad64)") (class "Default")
      (node (ref "U1") (pin "64") (pinfunction "PC7_64") (pintype "bidirectional"))
    )
    (net (code "96") (name "unconnected-(U1-PC8-Pad65)") (class "Default")
      (node (ref "U1") (pin "65") (pinfunction "PC8_65") (pintype "bidirectional"))
    )
    (net (code "97") (name "unconnected-(U1-PC9-Pad66)") (class "Default")
      (node (ref "U1") (pin "66") (pinfunction "PC9_66") (pintype "bidirectional"))
    )
    (net (code "98") (name "unconnected-(U1-PC10-Pad78)") (class "Default")
      (node (ref "U1") (pin "78") (pinfunction "PC10_78") (pintype "bidirectional"))
    )
    (net (code "99") (name "unconnected-(U1-PC11-Pad79)") (class "Default")
      (node (ref "U1") (pin "79") (pinfunction "PC11_79") (pintype "bidirectional"))
    )
    (net (code "100") (name "unconnected-(U1-PC13-TAMPER-RTC-Pad7)") (class "Default")
      (node (ref "U1") (pin "7") (pinfunction "PC13-TAMPER-RTC_7") (pintype "bidirectional"))
    )
    (net (code "101") (name "unconnected-(U1-PC14-OSC32_IN-Pad8)") (class "Default")
      (node (ref "U1") (pin "8") (pinfunction "PC14-OSC32_IN_8") (pintype "bidirectional"))
    )
    (net (code "102") (name "unconnected-(U1-PC15-OSC32_OUT-Pad9)") (class "Default")
      (node (ref "U1") (pin "9") (pinfunction "PC15-OSC32_OUT_9") (pintype "bidirectional"))
    )
    (net (code "103") (name "unconnected-(U1-PE0-Pad97)") (class "Default")
      (node (ref "U1") (pin "97") (pinfunction "PE0_97") (pintype "bidirectional"))
    )
    (net (code "104") (name "unconnected-(U1-PE1-Pad98)") (class "Default")
      (node (ref "U1") (pin "98") (pinfunction "PE1_98") (pintype "bidirectional"))
    )
    (net (code "105") (name "unconnected-(U1-PE3-Pad2)") (class "Default")
      (node (ref "U1") (pin "2") (pinfunction "PE3_2") (pintype "bidirectional"))
    )
    (net (code "106") (name "unconnected-(U1-PE4-Pad3)") (class "Default")
      (node (ref "U1") (pin "3") (pinfunction "PE4_3") (pintype "bidirectional"))
    )
    (net (code "107") (name "unconnected-(U1-PE5-Pad4)") (class "Default")
      (node (ref "U1") (pin "4") (pinfunction "PE5_4") (pintype "bidirectional"))
    )
    (net (code "108") (name "unconnected-(U1-PE6-Pad5)") (class "Default")
      (node (ref "U1") (pin "5") (pinfunction "PE6_5") (pintype "bidirectional"))
    )
    (net (code "109") (name "unconnected-(U1-VBAT-Pad6)") (class "Default")
      (node (ref "U1") (pin "6") (pinfunction "VBAT_6") (pintype "power_in"))
    )
    (net (code "110") (name "unconnected-(U1-VREF+-Pad21)") (class "Default")
      (node (ref "U1") (pin "21") (pinfunction "VREF+_21") (pintype "power_in"))
    )
    (net (code "111") (name "unconnected-(U1-VREF--Pad20)") (class "Default")
      (node (ref "U1") (pin "20") (pinfunction "VREF-_20") (pintype "power_in"))
    )
    (net (code "112") (name "unconnected-(U2-NC-Pad1)") (class "Default")
      (node (ref "U2") (pin "1") (pinfunction "NC_1") (pintype "passive"))
    )
    (net (code "113") (name "unconnected-(U2-NC-Pad7)") (class "Default")
      (node (ref "U2") (pin "7") (pinfunction "NC_7") (pintype "passive"))
    )
    (net (code "114") (name "unconnected-(U2-NC-Pad8)") (class "Default")
      (node (ref "U2") (pin "8") (pinfunction "NC_8") (pintype "passive"))
    )
    (net (code "115") (name "unconnected-(U2-NC-Pad11)") (class "Default")
      (node (ref "U2") (pin "11") (pinfunction "NC_11") (pintype "passive"))
    )
    (net (code "116") (name "unconnected-(U2-NC-Pad14)") (class "Default")
      (node (ref "U2") (pin "14") (pinfunction "NC_14") (pintype "passive"))
    )
    (net (code "117") (name "unconnected-(U3-EP-Pad11)") (class "Default")
      (node (ref "U3") (pin "11") (pinfunction "EP_11") (pintype "power_in"))
    )
    (net (code "118") (name "unconnected-(U3-NC-Pad6)") (class "Default")
      (node (ref "U3") (pin "6") (pinfunction "NC_6") (pintype "passive"))
    )
    (net (code "119") (name "unconnected-(U4-NC-Pad1)") (class "Default")
      (node (ref "U4") (pin "1") (pinfunction "NC_1") (pintype "passive"))
    )
    (net (code "120") (name "unconnected-(U4-PIO-Pad8)") (class "Default")
      (node (ref "U4") (pin "8") (pinfunction "PIO_8") (pintype "passive"))
    )
    (net (code "121") (name "unconnected-(U4-SNS-Pad7)") (class "Default")
      (node (ref "U4") (pin "7") (pinfunction "SNS_7") (pintype "passive"))
    )
    (net (code "122") (name "unconnected-(U8-NC-Pad3)") (class "Default")
      (node (ref "U8") (pin "3") (pinfunction "NC_3") (pintype "passive"))
    )
    (net (code "123") (name "unconnected-(U9-HOLD-Pad7)") (class "Default")
      (node (ref "U9") (pin "7") (pinfunction "HOLD_7") (pintype "passive"))
    )
    (net (code "124") (name "unconnected-(U9-WP-Pad3)") (class "Default")
      (node (ref "U9") (pin "3") (pinfunction "WP_3") (pintype "passive"))
    )
    (net (code "125") (name "unconnected-(X3-ID-Pad4)") (class "Default")
      (node (ref "X3") (pin "4") (pinfunction "ID_4") (pintype "passive"))
    )
  )
)
